# MCU.net
KiCad netlist of a schematic drawn in Altium Designer
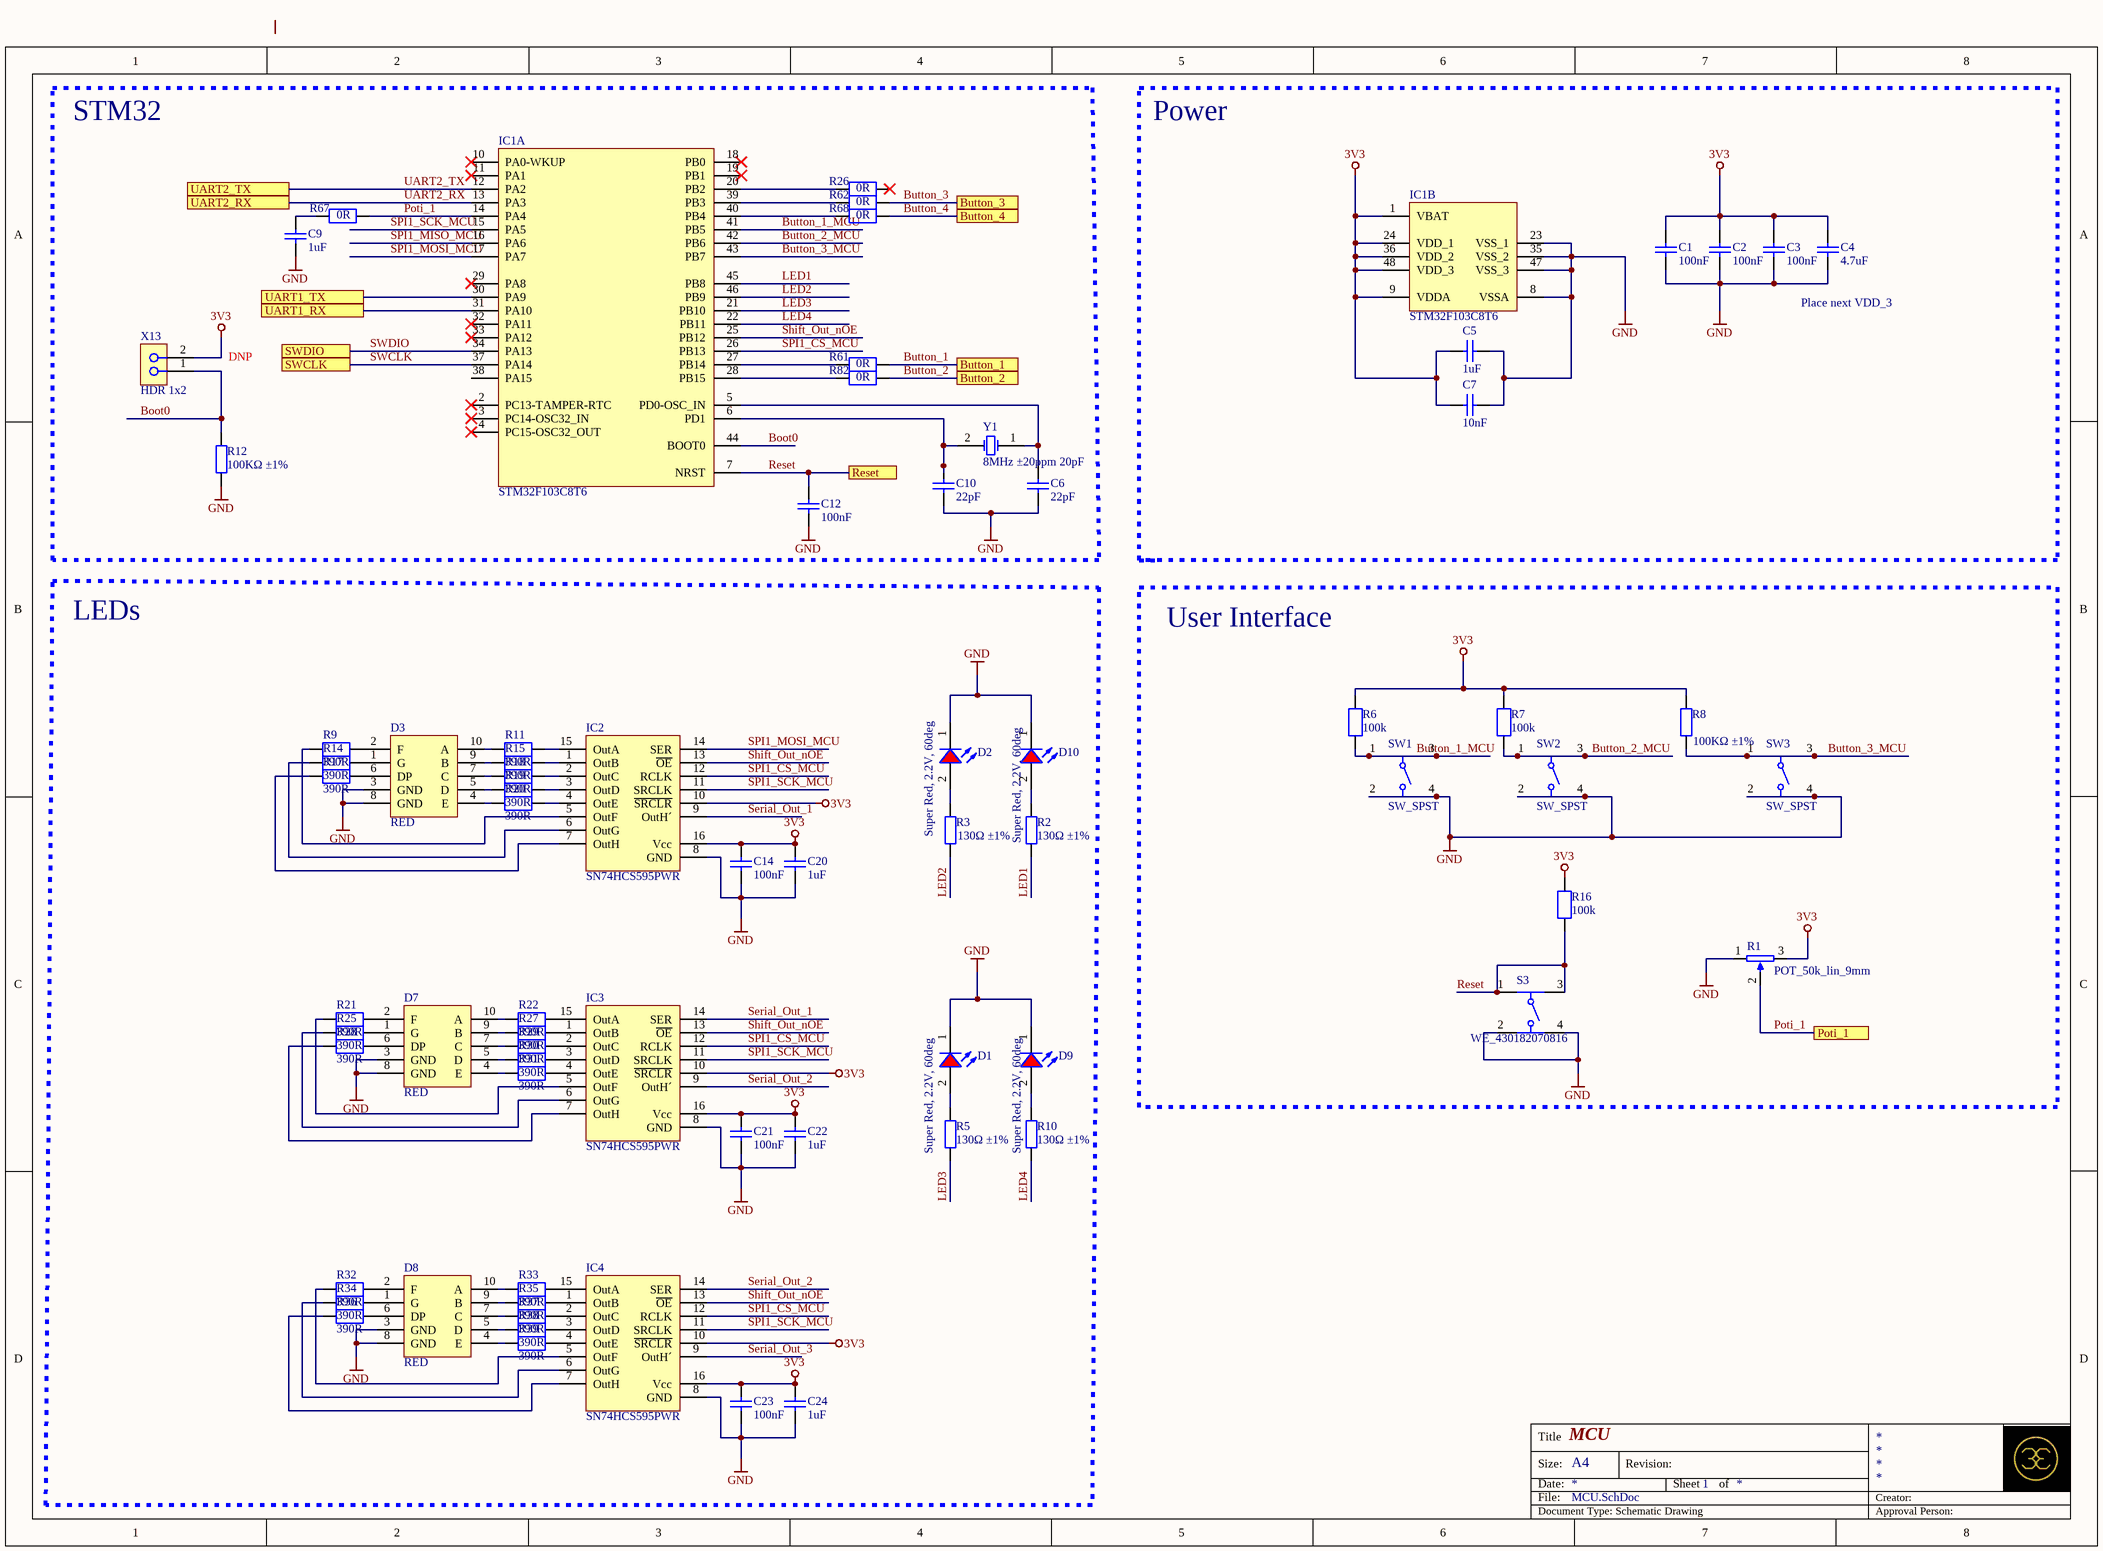
[diagram p0: MCU.SchDoc]

(export (version "E")
  (design (tool "Eeschema 10.0.6"))
  (components
    (comp (ref "C1")
      (value "100nF")
      (footprint "0603_C")
      (description "Chip capacitors")
      (fields (field (name "MANUFACTURER") "YAGEO") (field (name "PARTNUMBER") "CC0603KRX7R9BB104"))
      (libsource (lib "Cap") (part "0603 100nF (104) 10% 50V"))
    )
    (comp (ref "C2")
      (value "100nF")
      (footprint "0603_C")
      (description "Chip capacitors")
      (fields (field (name "MANUFACTURER") "YAGEO") (field (name "PARTNUMBER") "CC0603KRX7R9BB104"))
      (libsource (lib "Cap") (part "0603 100nF (104) 10% 50V"))
    )
    (comp (ref "C3")
      (value "100nF")
      (footprint "0603_C")
      (description "Chip capacitors")
      (fields (field (name "MANUFACTURER") "YAGEO") (field (name "PARTNUMBER") "CC0603KRX7R9BB104"))
      (libsource (lib "Cap") (part "0603 100nF (104) 10% 50V"))
    )
    (comp (ref "C4")
      (value "4.7uF")
      (footprint "0603_C")
      (description "Chip capacitors")
      (fields
        (field (name "MANUFACTURER") "Samsung Electro-Mechanics")
        (field (name "PARTNUMBER") "CL10A475KO8NNNC")
      )
      (libsource (lib "Cap") (part "0603 4.7uF (475) 10% 16V"))
    )
    (comp (ref "C5")
      (value "1uF")
      (footprint "0603_C")
      (description "Chip capacitors")
      (fields
        (field (name "MANUFACTURER") "Samsung Electro-Mechanics")
        (field (name "PARTNUMBER") "CL10A105KB8NNNC")
      )
      (libsource (lib "Cap") (part "0603 1uF (105) 10% 50V"))
    )
    (comp (ref "C6")
      (value "22pF")
      (footprint "0603_C")
      (description "Chip capacitors")
      (fields
        (field (name "MANUFACTURER") "Samsung Electro-Mechanics")
        (field (name "PARTNUMBER") "CL10C220JB8NNNC")
      )
      (libsource (lib "Cap") (part "0603 22pF (220) 5% 50V"))
    )
    (comp (ref "C7")
      (value "10nF")
      (footprint "0603_C")
      (description "Chip capacitors")
      (fields
        (field (name "MANUFACTURER") "Guangdong Fenghua Advanced Tech")
        (field (name "PARTNUMBER") "0603B103K500NT")
      )
      (libsource (lib "Cap") (part "0603 10nF (103) 10% 50V"))
    )
    (comp (ref "C9")
      (value "1uF")
      (footprint "0603_C")
      (description "Chip capacitors")
      (fields
        (field (name "MANUFACTURER") "Samsung Electro-Mechanics")
        (field (name "PARTNUMBER") "CL10A105KB8NNNC")
      )
      (libsource (lib "Cap") (part "0603 1uF (105) 10% 50V"))
    )
    (comp (ref "C10")
      (value "22pF")
      (footprint "0603_C")
      (description "Chip capacitors")
      (fields
        (field (name "MANUFACTURER") "Samsung Electro-Mechanics")
        (field (name "PARTNUMBER") "CL10C220JB8NNNC")
      )
      (libsource (lib "Cap") (part "0603 22pF (220) 5% 50V"))
    )
    (comp (ref "C12")
      (value "100nF")
      (footprint "0603_C")
      (description "Chip capacitors")
      (fields (field (name "MANUFACTURER") "YAGEO") (field (name "PARTNUMBER") "CC0603KRX7R9BB104"))
      (libsource (lib "Cap") (part "0603 100nF (104) 10% 50V"))
    )
    (comp (ref "C14")
      (value "100nF")
      (footprint "0603_C")
      (description "Chip capacitors")
      (fields (field (name "MANUFACTURER") "YAGEO") (field (name "PARTNUMBER") "CC0603KRX7R9BB104"))
      (libsource (lib "Cap") (part "0603 100nF (104) 10% 50V"))
    )
    (comp (ref "C20")
      (value "1uF")
      (footprint "0603_C")
      (description "Chip capacitors")
      (fields
        (field (name "MANUFACTURER") "Samsung Electro-Mechanics")
        (field (name "PARTNUMBER") "CL10A105KB8NNNC")
      )
      (libsource (lib "Cap") (part "0603 1uF (105) 10% 50V"))
    )
    (comp (ref "C21")
      (value "100nF")
      (footprint "0603_C")
      (description "Chip capacitors")
      (fields (field (name "MANUFACTURER") "YAGEO") (field (name "PARTNUMBER") "CC0603KRX7R9BB104"))
      (libsource (lib "Cap") (part "0603 100nF (104) 10% 50V"))
    )
    (comp (ref "C22")
      (value "1uF")
      (footprint "0603_C")
      (description "Chip capacitors")
      (fields
        (field (name "MANUFACTURER") "Samsung Electro-Mechanics")
        (field (name "PARTNUMBER") "CL10A105KB8NNNC")
      )
      (libsource (lib "Cap") (part "0603 1uF (105) 10% 50V"))
    )
    (comp (ref "C23")
      (value "100nF")
      (footprint "0603_C")
      (description "Chip capacitors")
      (fields (field (name "MANUFACTURER") "YAGEO") (field (name "PARTNUMBER") "CC0603KRX7R9BB104"))
      (libsource (lib "Cap") (part "0603 100nF (104) 10% 50V"))
    )
    (comp (ref "C24")
      (value "1uF")
      (footprint "0603_C")
      (description "Chip capacitors")
      (fields
        (field (name "MANUFACTURER") "Samsung Electro-Mechanics")
        (field (name "PARTNUMBER") "CL10A105KB8NNNC")
      )
      (libsource (lib "Cap") (part "0603 1uF (105) 10% 50V"))
    )
    (comp (ref "D1")
      (value "Super Red, 2.2V, 60deg")
      (footprint "WL-TMRC_3mm_10mm_space")
      (description "WL-TMRC THT Mono-color Round Color, size 3mm, Super Red, 2.2V, 60deg")
      (fields (field (name "PART NUMBER") "151031SS06000") (field (name "PUBLISHER") "Wurth Elektronik"))
      (libsource (lib "Diodes") (part "151031SS06000_Spacer_10mm"))
    )
    (comp (ref "D2")
      (value "Super Red, 2.2V, 60deg")
      (footprint "WL-TMRC_3mm_10mm_space")
      (description "WL-TMRC THT Mono-color Round Color, size 3mm, Super Red, 2.2V, 60deg")
      (fields (field (name "PART NUMBER") "151031SS06000") (field (name "PUBLISHER") "Wurth Elektronik"))
      (libsource (lib "Diodes") (part "151031SS06000_Spacer_10mm"))
    )
    (comp (ref "D3")
      (value "RED")
      (footprint "LTS-4301WC")
      (description "LED Displays & Accessories 1-Digit SMD Display Red Low-Cur .40")
      (fields (field (name "MANUFACTURER") "Lite-On") (field (name "MANUFACTURER PART NUMBER") "LTS-4301WC"))
      (libsource (lib "Diodes") (part "7-SEGMENT-10mm"))
    )
    (comp (ref "D7")
      (value "RED")
      (footprint "LTS-4301WC")
      (description "LED Displays & Accessories 1-Digit SMD Display Red Low-Cur .40")
      (fields (field (name "MANUFACTURER") "Lite-On") (field (name "MANUFACTURER PART NUMBER") "LTS-4301WC"))
      (libsource (lib "Diodes") (part "7-SEGMENT-10mm"))
    )
    (comp (ref "D8")
      (value "RED")
      (footprint "LTS-4301WC")
      (description "LED Displays & Accessories 1-Digit SMD Display Red Low-Cur .40")
      (fields (field (name "MANUFACTURER") "Lite-On") (field (name "MANUFACTURER PART NUMBER") "LTS-4301WC"))
      (libsource (lib "Diodes") (part "7-SEGMENT-10mm"))
    )
    (comp (ref "D9")
      (value "Super Red, 2.2V, 60deg")
      (footprint "WL-TMRC_3mm_10mm_space")
      (description "WL-TMRC THT Mono-color Round Color, size 3mm, Super Red, 2.2V, 60deg")
      (fields (field (name "PART NUMBER") "151031SS06000") (field (name "PUBLISHER") "Wurth Elektronik"))
      (libsource (lib "Diodes") (part "151031SS06000_Spacer_10mm"))
    )
    (comp (ref "D10")
      (value "Super Red, 2.2V, 60deg")
      (footprint "WL-TMRC_3mm_10mm_space")
      (description "WL-TMRC THT Mono-color Round Color, size 3mm, Super Red, 2.2V, 60deg")
      (fields (field (name "PART NUMBER") "151031SS06000") (field (name "PUBLISHER") "Wurth Elektronik"))
      (libsource (lib "Diodes") (part "151031SS06000_Spacer_10mm"))
    )
    (comp (ref "IC1")
      (value "STM32F103C8T6")
      (footprint "LQFP-48_7x7x05P")
      (description "ARM")
      (fields (field (name "MANUFACTURER") "STMicroelectronics"))
      (libsource (lib "ICs") (part "STM32F103C8T6"))
    )
    (comp (ref "IC2")
      (value "SN74HCS595PWR")
      (footprint "TSOP65P640X120-16N_2")
      (description "Counter Shift Registers 8-bit serial-in/parallel-out shift register 16-TSSOP -40 to 125")
      (fields (field (name "MANUFACTURER") "Texas Instruments"))
      (libsource (lib "ICs") (part "IC_SN74HCS595"))
    )
    (comp (ref "IC3")
      (value "SN74HCS595PWR")
      (footprint "TSOP65P640X120-16N_2")
      (description "Counter Shift Registers 8-bit serial-in/parallel-out shift register 16-TSSOP -40 to 125")
      (fields (field (name "MANUFACTURER") "Texas Instruments"))
      (libsource (lib "ICs") (part "IC_SN74HCS595"))
    )
    (comp (ref "IC4")
      (value "SN74HCS595PWR")
      (footprint "TSOP65P640X120-16N_2")
      (description "Counter Shift Registers 8-bit serial-in/parallel-out shift register 16-TSSOP -40 to 125")
      (fields (field (name "MANUFACTURER") "Texas Instruments"))
      (libsource (lib "ICs") (part "IC_SN74HCS595"))
    )
    (comp (ref "R1")
      (value "POT_50k_lin_9mm")
      (footprint "PTV09")
      (description "Potentiometers PANEL CONTROL - 9MM-ST-CA 50 kohms 30 mm")
      (fields
        (field (name "MANUFACTURER") "Bourns")
        (field (name "MANUFACTURER PART NUMBER") "PTV09A-4030S-A503")
      )
      (libsource (lib "Resistors") (part "POT_50k_lin_9mm"))
    )
    (comp (ref "R2")
      (value "130Ω ±1%")
      (footprint "0603_R")
      (description "Chip resistor")
      (fields (field (name "MANUFACTURER") "Uniroyal Elec") (field (name "PARTNUMBER") "0603WAF1300T5E"))
      (libsource (lib "RES") (part "0603 130R (1300) 1%"))
    )
    (comp (ref "R3")
      (value "130Ω ±1%")
      (footprint "0603_R")
      (description "Chip resistor")
      (fields (field (name "MANUFACTURER") "Uniroyal Elec") (field (name "PARTNUMBER") "0603WAF1300T5E"))
      (libsource (lib "RES") (part "0603 130R (1300) 1%"))
    )
    (comp (ref "R5")
      (value "130Ω ±1%")
      (footprint "0603_R")
      (description "Chip resistor")
      (fields (field (name "MANUFACTURER") "Uniroyal Elec") (field (name "PARTNUMBER") "0603WAF1300T5E"))
      (libsource (lib "RES") (part "0603 130R (1300) 1%"))
    )
    (comp (ref "R6")
      (value "100k")
      (footprint "RESC2012X70N")
      (description "Thick Film Resistors - SMD 1/8watt 100Kohms 1% 100ppm")
      (fields
        (field (name "MANUFACTURER") "Vishay / Dale")
        (field (name "MANUFACTURER PART NUMBER") "CRCW0805100KFKEA")
      )
      (libsource (lib "Resistors") (part "RES_100k_0805"))
    )
    (comp (ref "R7")
      (value "100k")
      (footprint "RESC2012X70N")
      (description "Thick Film Resistors - SMD 1/8watt 100Kohms 1% 100ppm")
      (fields
        (field (name "MANUFACTURER") "Vishay / Dale")
        (field (name "MANUFACTURER PART NUMBER") "CRCW0805100KFKEA")
      )
      (libsource (lib "Resistors") (part "RES_100k_0805"))
    )
    (comp (ref "R8")
      (value "100KΩ ±1%")
      (footprint "0603_R")
      (description "Chip resistor")
      (fields (field (name "MANUFACTURER") "Uniroyal Elec") (field (name "PARTNUMBER") "0603WAF1003T5E"))
      (libsource (lib "RES") (part "0603 100K (1003) 1%"))
    )
    (comp (ref "R9")
      (value "390R")
      (footprint "RESC2012X70N")
      (description "Thick Film Resistors - SMD 1/8Watt 390ohms 1% Commercial Use")
      (fields
        (field (name "MANUFACTURER") "Vishay / Dale")
        (field (name "MANUFACTURER PART NUMBER") "CRCW0805390RFKEA")
      )
      (libsource (lib "Resistors") (part "RES_390R_0805"))
    )
    (comp (ref "R10")
      (value "130Ω ±1%")
      (footprint "0603_R")
      (description "Chip resistor")
      (fields (field (name "MANUFACTURER") "Uniroyal Elec") (field (name "PARTNUMBER") "0603WAF1300T5E"))
      (libsource (lib "RES") (part "0603 130R (1300) 1%"))
    )
    (comp (ref "R11")
      (value "390R")
      (footprint "RESC2012X70N")
      (description "Thick Film Resistors - SMD 1/8Watt 390ohms 1% Commercial Use")
      (fields
        (field (name "MANUFACTURER") "Vishay / Dale")
        (field (name "MANUFACTURER PART NUMBER") "CRCW0805390RFKEA")
      )
      (libsource (lib "Resistors") (part "RES_390R_0805"))
    )
    (comp (ref "R12")
      (value "100KΩ ±1%")
      (footprint "0603_R")
      (description "Chip resistor")
      (fields (field (name "MANUFACTURER") "Uniroyal Elec") (field (name "PARTNUMBER") "0603WAF1003T5E"))
      (libsource (lib "RES") (part "0603 100K (1003) 1%"))
    )
    (comp (ref "R14")
      (value "390R")
      (footprint "RESC2012X70N")
      (description "Thick Film Resistors - SMD 1/8Watt 390ohms 1% Commercial Use")
      (fields
        (field (name "MANUFACTURER") "Vishay / Dale")
        (field (name "MANUFACTURER PART NUMBER") "CRCW0805390RFKEA")
      )
      (libsource (lib "Resistors") (part "RES_390R_0805"))
    )
    (comp (ref "R15")
      (value "390R")
      (footprint "RESC2012X70N")
      (description "Thick Film Resistors - SMD 1/8Watt 390ohms 1% Commercial Use")
      (fields
        (field (name "MANUFACTURER") "Vishay / Dale")
        (field (name "MANUFACTURER PART NUMBER") "CRCW0805390RFKEA")
      )
      (libsource (lib "Resistors") (part "RES_390R_0805"))
    )
    (comp (ref "R16")
      (value "100k")
      (footprint "RESC2012X70N")
      (description "Thick Film Resistors - SMD 1/8watt 100Kohms 1% 100ppm")
      (fields
        (field (name "MANUFACTURER") "Vishay / Dale")
        (field (name "MANUFACTURER PART NUMBER") "CRCW0805100KFKEA")
      )
      (libsource (lib "Resistors") (part "RES_100k_0805"))
    )
    (comp (ref "R17")
      (value "390R")
      (footprint "RESC2012X70N")
      (description "Thick Film Resistors - SMD 1/8Watt 390ohms 1% Commercial Use")
      (fields
        (field (name "MANUFACTURER") "Vishay / Dale")
        (field (name "MANUFACTURER PART NUMBER") "CRCW0805390RFKEA")
      )
      (libsource (lib "Resistors") (part "RES_390R_0805"))
    )
    (comp (ref "R18")
      (value "390R")
      (footprint "RESC2012X70N")
      (description "Thick Film Resistors - SMD 1/8Watt 390ohms 1% Commercial Use")
      (fields
        (field (name "MANUFACTURER") "Vishay / Dale")
        (field (name "MANUFACTURER PART NUMBER") "CRCW0805390RFKEA")
      )
      (libsource (lib "Resistors") (part "RES_390R_0805"))
    )
    (comp (ref "R19")
      (value "390R")
      (footprint "RESC2012X70N")
      (description "Thick Film Resistors - SMD 1/8Watt 390ohms 1% Commercial Use")
      (fields
        (field (name "MANUFACTURER") "Vishay / Dale")
        (field (name "MANUFACTURER PART NUMBER") "CRCW0805390RFKEA")
      )
      (libsource (lib "Resistors") (part "RES_390R_0805"))
    )
    (comp (ref "R20")
      (value "390R")
      (footprint "RESC2012X70N")
      (description "Thick Film Resistors - SMD 1/8Watt 390ohms 1% Commercial Use")
      (fields
        (field (name "MANUFACTURER") "Vishay / Dale")
        (field (name "MANUFACTURER PART NUMBER") "CRCW0805390RFKEA")
      )
      (libsource (lib "Resistors") (part "RES_390R_0805"))
    )
    (comp (ref "R21")
      (value "390R")
      (footprint "RESC2012X70N")
      (description "Thick Film Resistors - SMD 1/8Watt 390ohms 1% Commercial Use")
      (fields
        (field (name "MANUFACTURER") "Vishay / Dale")
        (field (name "MANUFACTURER PART NUMBER") "CRCW0805390RFKEA")
      )
      (libsource (lib "Resistors") (part "RES_390R_0805"))
    )
    (comp (ref "R22")
      (value "390R")
      (footprint "RESC2012X70N")
      (description "Thick Film Resistors - SMD 1/8Watt 390ohms 1% Commercial Use")
      (fields
        (field (name "MANUFACTURER") "Vishay / Dale")
        (field (name "MANUFACTURER PART NUMBER") "CRCW0805390RFKEA")
      )
      (libsource (lib "Resistors") (part "RES_390R_0805"))
    )
    (comp (ref "R25")
      (value "390R")
      (footprint "RESC2012X70N")
      (description "Thick Film Resistors - SMD 1/8Watt 390ohms 1% Commercial Use")
      (fields
        (field (name "MANUFACTURER") "Vishay / Dale")
        (field (name "MANUFACTURER PART NUMBER") "CRCW0805390RFKEA")
      )
      (libsource (lib "Resistors") (part "RES_390R_0805"))
    )
    (comp (ref "R26")
      (value "0R")
      (footprint "RESC1608X55N")
      (description "Thick Film Resistors - SMD 1/10watt ZEROohm Jumper")
      (fields
        (field (name "MANUFACTURER") "Vishay")
        (field (name "MANUFACTURER PART NUMBER") "CRCW06030000Z0EA")
      )
      (libsource (lib "Resistors") (part "RES_0R_0603"))
    )
    (comp (ref "R27")
      (value "390R")
      (footprint "RESC2012X70N")
      (description "Thick Film Resistors - SMD 1/8Watt 390ohms 1% Commercial Use")
      (fields
        (field (name "MANUFACTURER") "Vishay / Dale")
        (field (name "MANUFACTURER PART NUMBER") "CRCW0805390RFKEA")
      )
      (libsource (lib "Resistors") (part "RES_390R_0805"))
    )
    (comp (ref "R28")
      (value "390R")
      (footprint "RESC2012X70N")
      (description "Thick Film Resistors - SMD 1/8Watt 390ohms 1% Commercial Use")
      (fields
        (field (name "MANUFACTURER") "Vishay / Dale")
        (field (name "MANUFACTURER PART NUMBER") "CRCW0805390RFKEA")
      )
      (libsource (lib "Resistors") (part "RES_390R_0805"))
    )
    (comp (ref "R29")
      (value "390R")
      (footprint "RESC2012X70N")
      (description "Thick Film Resistors - SMD 1/8Watt 390ohms 1% Commercial Use")
      (fields
        (field (name "MANUFACTURER") "Vishay / Dale")
        (field (name "MANUFACTURER PART NUMBER") "CRCW0805390RFKEA")
      )
      (libsource (lib "Resistors") (part "RES_390R_0805"))
    )
    (comp (ref "R30")
      (value "390R")
      (footprint "RESC2012X70N")
      (description "Thick Film Resistors - SMD 1/8Watt 390ohms 1% Commercial Use")
      (fields
        (field (name "MANUFACTURER") "Vishay / Dale")
        (field (name "MANUFACTURER PART NUMBER") "CRCW0805390RFKEA")
      )
      (libsource (lib "Resistors") (part "RES_390R_0805"))
    )
    (comp (ref "R31")
      (value "390R")
      (footprint "RESC2012X70N")
      (description "Thick Film Resistors - SMD 1/8Watt 390ohms 1% Commercial Use")
      (fields
        (field (name "MANUFACTURER") "Vishay / Dale")
        (field (name "MANUFACTURER PART NUMBER") "CRCW0805390RFKEA")
      )
      (libsource (lib "Resistors") (part "RES_390R_0805"))
    )
    (comp (ref "R32")
      (value "390R")
      (footprint "RESC2012X70N")
      (description "Thick Film Resistors - SMD 1/8Watt 390ohms 1% Commercial Use")
      (fields
        (field (name "MANUFACTURER") "Vishay / Dale")
        (field (name "MANUFACTURER PART NUMBER") "CRCW0805390RFKEA")
      )
      (libsource (lib "Resistors") (part "RES_390R_0805"))
    )
    (comp (ref "R33")
      (value "390R")
      (footprint "RESC2012X70N")
      (description "Thick Film Resistors - SMD 1/8Watt 390ohms 1% Commercial Use")
      (fields
        (field (name "MANUFACTURER") "Vishay / Dale")
        (field (name "MANUFACTURER PART NUMBER") "CRCW0805390RFKEA")
      )
      (libsource (lib "Resistors") (part "RES_390R_0805"))
    )
    (comp (ref "R34")
      (value "390R")
      (footprint "RESC2012X70N")
      (description "Thick Film Resistors - SMD 1/8Watt 390ohms 1% Commercial Use")
      (fields
        (field (name "MANUFACTURER") "Vishay / Dale")
        (field (name "MANUFACTURER PART NUMBER") "CRCW0805390RFKEA")
      )
      (libsource (lib "Resistors") (part "RES_390R_0805"))
    )
    (comp (ref "R35")
      (value "390R")
      (footprint "RESC2012X70N")
      (description "Thick Film Resistors - SMD 1/8Watt 390ohms 1% Commercial Use")
      (fields
        (field (name "MANUFACTURER") "Vishay / Dale")
        (field (name "MANUFACTURER PART NUMBER") "CRCW0805390RFKEA")
      )
      (libsource (lib "Resistors") (part "RES_390R_0805"))
    )
    (comp (ref "R36")
      (value "390R")
      (footprint "RESC2012X70N")
      (description "Thick Film Resistors - SMD 1/8Watt 390ohms 1% Commercial Use")
      (fields
        (field (name "MANUFACTURER") "Vishay / Dale")
        (field (name "MANUFACTURER PART NUMBER") "CRCW0805390RFKEA")
      )
      (libsource (lib "Resistors") (part "RES_390R_0805"))
    )
    (comp (ref "R37")
      (value "390R")
      (footprint "RESC2012X70N")
      (description "Thick Film Resistors - SMD 1/8Watt 390ohms 1% Commercial Use")
      (fields
        (field (name "MANUFACTURER") "Vishay / Dale")
        (field (name "MANUFACTURER PART NUMBER") "CRCW0805390RFKEA")
      )
      (libsource (lib "Resistors") (part "RES_390R_0805"))
    )
    (comp (ref "R38")
      (value "390R")
      (footprint "RESC2012X70N")
      (description "Thick Film Resistors - SMD 1/8Watt 390ohms 1% Commercial Use")
      (fields
        (field (name "MANUFACTURER") "Vishay / Dale")
        (field (name "MANUFACTURER PART NUMBER") "CRCW0805390RFKEA")
      )
      (libsource (lib "Resistors") (part "RES_390R_0805"))
    )
    (comp (ref "R39")
      (value "390R")
      (footprint "RESC2012X70N")
      (description "Thick Film Resistors - SMD 1/8Watt 390ohms 1% Commercial Use")
      (fields
        (field (name "MANUFACTURER") "Vishay / Dale")
        (field (name "MANUFACTURER PART NUMBER") "CRCW0805390RFKEA")
      )
      (libsource (lib "Resistors") (part "RES_390R_0805"))
    )
    (comp (ref "R61")
      (value "0R")
      (footprint "RESC1608X55N")
      (description "Thick Film Resistors - SMD 1/10watt ZEROohm Jumper")
      (fields
        (field (name "MANUFACTURER") "Vishay")
        (field (name "MANUFACTURER PART NUMBER") "CRCW06030000Z0EA")
      )
      (libsource (lib "Resistors") (part "RES_0R_0603"))
    )
    (comp (ref "R62")
      (value "0R")
      (footprint "RESC1608X55N")
      (description "Thick Film Resistors - SMD 1/10watt ZEROohm Jumper")
      (fields
        (field (name "MANUFACTURER") "Vishay")
        (field (name "MANUFACTURER PART NUMBER") "CRCW06030000Z0EA")
      )
      (libsource (lib "Resistors") (part "RES_0R_0603"))
    )
    (comp (ref "R67")
      (value "0R")
      (footprint "RESC1608X55N")
      (description "Thick Film Resistors - SMD 1/10watt ZEROohm Jumper")
      (fields
        (field (name "MANUFACTURER") "Vishay")
        (field (name "MANUFACTURER PART NUMBER") "CRCW06030000Z0EA")
      )
      (libsource (lib "Resistors") (part "RES_0R_0603"))
    )
    (comp (ref "R68")
      (value "0R")
      (footprint "RESC1608X55N")
      (description "Thick Film Resistors - SMD 1/10watt ZEROohm Jumper")
      (fields
        (field (name "MANUFACTURER") "Vishay")
        (field (name "MANUFACTURER PART NUMBER") "CRCW06030000Z0EA")
      )
      (libsource (lib "Resistors") (part "RES_0R_0603"))
    )
    (comp (ref "R82")
      (value "0R")
      (footprint "RESC1608X55N")
      (description "Thick Film Resistors - SMD 1/10watt ZEROohm Jumper")
      (fields
        (field (name "MANUFACTURER") "Vishay")
        (field (name "MANUFACTURER PART NUMBER") "CRCW06030000Z0EA")
      )
      (libsource (lib "Resistors") (part "RES_0R_0603"))
    )
    (comp (ref "S3")
      (value "WE_430182070816")
      (footprint "430182070816")
      (description "WS-TASV SMT Tact Switch 6x6mm, height 7mm, 160gf")
      (fields (field (name "PART NUMBER") "430182070816") (field (name "PUBLISHER") "Wurth Elektronik"))
      (libsource (lib "Switches") (part "WE_430182070816"))
    )
    (comp (ref "SW1")
      (value "SW_SPST")
      (footprint "TL1105D")
      (description "Tastschalter SPST-Schließer Von oben betätigt Durchkontaktierung")
      (fields
        (field (name "MANUFACTURER") "E-Switch")
        (field (name "MANUFACTURER PART NUMBER") "TL1105DF160Q")
      )
      (libsource (lib "Switches") (part "SW_ TL1105DF160Q"))
    )
    (comp (ref "SW2")
      (value "SW_SPST")
      (footprint "TL1105D")
      (description "Tastschalter SPST-Schließer Von oben betätigt Durchkontaktierung")
      (fields
        (field (name "MANUFACTURER") "E-Switch")
        (field (name "MANUFACTURER PART NUMBER") "TL1105DF160Q")
      )
      (libsource (lib "Switches") (part "SW_ TL1105DF160Q"))
    )
    (comp (ref "SW3")
      (value "SW_SPST")
      (footprint "TL1105D")
      (description "Tastschalter SPST-Schließer Von oben betätigt Durchkontaktierung")
      (fields
        (field (name "MANUFACTURER") "E-Switch")
        (field (name "MANUFACTURER PART NUMBER") "TL1105DF160Q")
      )
      (libsource (lib "Switches") (part "SW_ TL1105DF160Q"))
    )
    (comp (ref "X13")
      (value "HDR 1x2")
      (footprint "CON_HEADER2.54_1x2W")
      (description "Board-to-Board-Steckverbinder, 2.54 mm, 2 Kontakt(e), Stiftleiste 1-Reihig")
      (fields
        (field (name "MANUFACTURER") "Samtec")
        (field (name "MANUFACTURER PART NUMBER") "TSW-102-07-T-S")
      )
      (libsource (lib "Connectors") (part "CON_HEADER_1X2"))
    )
    (comp (ref "Y1")
      (value "8MHz ±20ppm 20pF")
      (footprint "SMD-5032_2P")
      (description "贴片晶振")
      (libsource (lib "CrystalOscillator") (part "SMD-5032_2P 8MHz 20ppm 20pF"))
    )
  )
  (nets
    (net (code "1") (name "/Boot0") (class "Default")
      (node (ref "IC1") (pin "44") (pinfunction "BOOT0_44") (pintype "passive"))
      (node (ref "R12") (pin "2") (pinfunction "2_2") (pintype "passive"))
      (node (ref "X13") (pin "1") (pinfunction "1_1") (pintype "passive"))
    )
    (net (code "2") (name "/Button_1") (class "Default")
      (node (ref "R61") (pin "2") (pinfunction "2_2") (pintype "passive"))
    )
    (net (code "3") (name "/Button_1_MCU") (class "Default")
      (node (ref "IC1") (pin "41") (pinfunction "PB5_41") (pintype "passive"))
      (node (ref "R6") (pin "1") (pinfunction "1_1") (pintype "passive"))
      (node (ref "SW1") (pin "1") (pinfunction "1_1") (pintype "passive"))
      (node (ref "SW1") (pin "3") (pinfunction "3_3") (pintype "passive"))
    )
    (net (code "4") (name "/Button_2") (class "Default")
      (node (ref "R82") (pin "2") (pinfunction "2_2") (pintype "passive"))
    )
    (net (code "5") (name "/Button_2_MCU") (class "Default")
      (node (ref "IC1") (pin "42") (pinfunction "PB6_42") (pintype "passive"))
      (node (ref "R7") (pin "1") (pinfunction "1_1") (pintype "passive"))
      (node (ref "SW2") (pin "1") (pinfunction "1_1") (pintype "passive"))
      (node (ref "SW2") (pin "3") (pinfunction "3_3") (pintype "passive"))
    )
    (net (code "6") (name "/Button_3") (class "Default")
      (node (ref "R62") (pin "2") (pinfunction "2_2") (pintype "passive"))
    )
    (net (code "7") (name "/Button_3_MCU") (class "Default")
      (node (ref "IC1") (pin "43") (pinfunction "PB7_43") (pintype "passive"))
      (node (ref "R8") (pin "1") (pinfunction "1_1") (pintype "passive"))
      (node (ref "SW3") (pin "1") (pinfunction "1_1") (pintype "passive"))
      (node (ref "SW3") (pin "3") (pinfunction "3_3") (pintype "passive"))
    )
    (net (code "8") (name "/Button_4") (class "Default")
      (node (ref "R68") (pin "2") (pinfunction "2_2") (pintype "passive"))
    )
    (net (code "9") (name "/LED1") (class "Default")
      (node (ref "IC1") (pin "45") (pinfunction "PB8_45") (pintype "passive"))
      (node (ref "R2") (pin "2") (pinfunction "2_2") (pintype "passive"))
    )
    (net (code "10") (name "/LED2") (class "Default")
      (node (ref "IC1") (pin "46") (pinfunction "PB9_46") (pintype "passive"))
      (node (ref "R3") (pin "2") (pinfunction "2_2") (pintype "passive"))
    )
    (net (code "11") (name "/LED3") (class "Default")
      (node (ref "IC1") (pin "21") (pinfunction "PB10_21") (pintype "passive"))
      (node (ref "R5") (pin "2") (pinfunction "2_2") (pintype "passive"))
    )
    (net (code "12") (name "/LED4") (class "Default")
      (node (ref "IC1") (pin "22") (pinfunction "PB11_22") (pintype "passive"))
      (node (ref "R10") (pin "2") (pinfunction "2_2") (pintype "passive"))
    )
    (net (code "13") (name "/Poti_1") (class "Default")
      (node (ref "IC1") (pin "14") (pinfunction "PA4_14") (pintype "passive"))
      (node (ref "R1") (pin "2") (pinfunction "2_2") (pintype "passive"))
      (node (ref "R67") (pin "2") (pinfunction "2_2") (pintype "passive"))
    )
    (net (code "14") (name "/Reset") (class "Default")
      (node (ref "C12") (pin "2") (pinfunction "2_2") (pintype "passive"))
      (node (ref "IC1") (pin "7") (pinfunction "NRST_7") (pintype "passive"))
      (node (ref "R16") (pin "1") (pinfunction "1_1") (pintype "passive"))
      (node (ref "S3") (pin "1") (pinfunction "1_1") (pintype "passive"))
      (node (ref "S3") (pin "3") (pinfunction "3_3") (pintype "passive"))
    )
    (net (code "15") (name "/SPI1_CS_MCU") (class "Default")
      (node (ref "IC1") (pin "26") (pinfunction "PB13_26") (pintype "passive"))
      (node (ref "IC2") (pin "12") (pinfunction "RCLK_12") (pintype "passive"))
      (node (ref "IC3") (pin "12") (pinfunction "RCLK_12") (pintype "passive"))
      (node (ref "IC4") (pin "12") (pinfunction "RCLK_12") (pintype "passive"))
    )
    (net (code "16") (name "/SPI1_MISO_MCU") (class "Default")
      (node (ref "IC1") (pin "16") (pinfunction "PA6_16") (pintype "passive"))
    )
    (net (code "17") (name "/SPI1_MOSI_MCU") (class "Default")
      (node (ref "IC1") (pin "17") (pinfunction "PA7_17") (pintype "passive"))
      (node (ref "IC2") (pin "14") (pinfunction "SER_14") (pintype "passive"))
    )
    (net (code "18") (name "/SPI1_SCK_MCU") (class "Default")
      (node (ref "IC1") (pin "15") (pinfunction "PA5_15") (pintype "passive"))
      (node (ref "IC2") (pin "11") (pinfunction "SRCLK_11") (pintype "passive"))
      (node (ref "IC3") (pin "11") (pinfunction "SRCLK_11") (pintype "passive"))
      (node (ref "IC4") (pin "11") (pinfunction "SRCLK_11") (pintype "passive"))
    )
    (net (code "19") (name "/SWCLK") (class "Default")
      (node (ref "IC1") (pin "37") (pinfunction "PA14_37") (pintype "passive"))
    )
    (net (code "20") (name "/SWDIO") (class "Default")
      (node (ref "IC1") (pin "34") (pinfunction "PA13_34") (pintype "passive"))
    )
    (net (code "21") (name "/Serial_Out_1") (class "Default")
      (node (ref "IC2") (pin "9") (pinfunction "OutH´_9") (pintype "passive"))
      (node (ref "IC3") (pin "14") (pinfunction "SER_14") (pintype "passive"))
    )
    (net (code "22") (name "/Serial_Out_2") (class "Default")
      (node (ref "IC3") (pin "9") (pinfunction "OutH´_9") (pintype "passive"))
      (node (ref "IC4") (pin "14") (pinfunction "SER_14") (pintype "passive"))
    )
    (net (code "23") (name "/Serial_Out_3") (class "Default")
      (node (ref "IC4") (pin "9") (pinfunction "OutH´_9") (pintype "passive"))
    )
    (net (code "24") (name "/Shift_Out_nOE") (class "Default")
      (node (ref "IC1") (pin "25") (pinfunction "PB12_25") (pintype "passive"))
      (node (ref "IC2") (pin "13") (pinfunction "~{OE}_13") (pintype "passive"))
      (node (ref "IC3") (pin "13") (pinfunction "~{OE}_13") (pintype "passive"))
      (node (ref "IC4") (pin "13") (pinfunction "~{OE}_13") (pintype "passive"))
    )
    (net (code "25") (name "/UART1_RX") (class "Default")
      (node (ref "IC1") (pin "31") (pinfunction "PA10_31") (pintype "passive"))
    )
    (net (code "26") (name "/UART1_TX") (class "Default")
      (node (ref "IC1") (pin "30") (pinfunction "PA9_30") (pintype "passive"))
    )
    (net (code "27") (name "/UART2_RX") (class "Default")
      (node (ref "IC1") (pin "13") (pinfunction "PA3_13") (pintype "passive"))
    )
    (net (code "28") (name "/UART2_TX") (class "Default")
      (node (ref "IC1") (pin "12") (pinfunction "PA2_12") (pintype "passive"))
    )
    (net (code "29") (name "3V3") (class "Default")
      (node (ref "C1") (pin "2") (pinfunction "2_2") (pintype "passive"))
      (node (ref "C14") (pin "2") (pinfunction "2_2") (pintype "passive"))
      (node (ref "C2") (pin "2") (pinfunction "2_2") (pintype "passive"))
      (node (ref "C20") (pin "2") (pinfunction "2_2") (pintype "passive"))
      (node (ref "C21") (pin "2") (pinfunction "2_2") (pintype "passive"))
      (node (ref "C22") (pin "2") (pinfunction "2_2") (pintype "passive"))
      (node (ref "C23") (pin "2") (pinfunction "2_2") (pintype "passive"))
      (node (ref "C24") (pin "2") (pinfunction "2_2") (pintype "passive"))
      (node (ref "C3") (pin "2") (pinfunction "2_2") (pintype "passive"))
      (node (ref "C4") (pin "2") (pinfunction "2_2") (pintype "passive"))
      (node (ref "C5") (pin "1") (pinfunction "1_1") (pintype "passive"))
      (node (ref "C7") (pin "1") (pinfunction "1_1") (pintype "passive"))
      (node (ref "IC1") (pin "1") (pinfunction "VBAT_1") (pintype "power_in"))
      (node (ref "IC1") (pin "24") (pinfunction "VDD_1_24") (pintype "power_in"))
      (node (ref "IC1") (pin "36") (pinfunction "VDD_2_36") (pintype "power_in"))
      (node (ref "IC1") (pin "48") (pinfunction "VDD_3_48") (pintype "power_in"))
      (node (ref "IC1") (pin "9") (pinfunction "VDDA_9") (pintype "power_in"))
      (node (ref "IC2") (pin "10") (pinfunction "~{SRCLR}_10") (pintype "passive"))
      (node (ref "IC2") (pin "16") (pinfunction "Vcc_16") (pintype "passive"))
      (node (ref "IC3") (pin "10") (pinfunction "~{SRCLR}_10") (pintype "passive"))
      (node (ref "IC3") (pin "16") (pinfunction "Vcc_16") (pintype "passive"))
      (node (ref "IC4") (pin "10") (pinfunction "~{SRCLR}_10") (pintype "passive"))
      (node (ref "IC4") (pin "16") (pinfunction "Vcc_16") (pintype "passive"))
      (node (ref "R1") (pin "3") (pinfunction "3_3") (pintype "passive"))
      (node (ref "R16") (pin "2") (pinfunction "2_2") (pintype "passive"))
      (node (ref "R6") (pin "2") (pinfunction "2_2") (pintype "passive"))
      (node (ref "R7") (pin "2") (pinfunction "2_2") (pintype "passive"))
      (node (ref "R8") (pin "2") (pinfunction "2_2") (pintype "passive"))
      (node (ref "X13") (pin "2") (pinfunction "2_2") (pintype "passive"))
    )
    (net (code "30") (name "GND") (class "Default")
      (node (ref "C1") (pin "1") (pinfunction "1_1") (pintype "passive"))
      (node (ref "C10") (pin "2") (pinfunction "2_2") (pintype "passive"))
      (node (ref "C12") (pin "1") (pinfunction "1_1") (pintype "passive"))
      (node (ref "C14") (pin "1") (pinfunction "1_1") (pintype "passive"))
      (node (ref "C2") (pin "1") (pinfunction "1_1") (pintype "passive"))
      (node (ref "C20") (pin "1") (pinfunction "1_1") (pintype "passive"))
      (node (ref "C21") (pin "1") (pinfunction "1_1") (pintype "passive"))
      (node (ref "C22") (pin "1") (pinfunction "1_1") (pintype "passive"))
      (node (ref "C23") (pin "1") (pinfunction "1_1") (pintype "passive"))
      (node (ref "C24") (pin "1") (pinfunction "1_1") (pintype "passive"))
      (node (ref "C3") (pin "1") (pinfunction "1_1") (pintype "passive"))
      (node (ref "C4") (pin "1") (pinfunction "1_1") (pintype "passive"))
      (node (ref "C5") (pin "2") (pinfunction "2_2") (pintype "passive"))
      (node (ref "C6") (pin "2") (pinfunction "2_2") (pintype "passive"))
      (node (ref "C7") (pin "2") (pinfunction "2_2") (pintype "passive"))
      (node (ref "C9") (pin "2") (pinfunction "2_2") (pintype "passive"))
      (node (ref "D1") (pin "1") (pinfunction "K_1") (pintype "passive"))
      (node (ref "D10") (pin "1") (pinfunction "K_1") (pintype "passive"))
      (node (ref "D2") (pin "1") (pinfunction "K_1") (pintype "passive"))
      (node (ref "D3") (pin "3") (pinfunction "GND_3") (pintype "passive"))
      (node (ref "D3") (pin "8") (pinfunction "GND_8") (pintype "passive"))
      (node (ref "D7") (pin "3") (pinfunction "GND_3") (pintype "passive"))
      (node (ref "D7") (pin "8") (pinfunction "GND_8") (pintype "passive"))
      (node (ref "D8") (pin "3") (pinfunction "GND_3") (pintype "passive"))
      (node (ref "D8") (pin "8") (pinfunction "GND_8") (pintype "passive"))
      (node (ref "D9") (pin "1") (pinfunction "K_1") (pintype "passive"))
      (node (ref "IC1") (pin "23") (pinfunction "VSS_1_23") (pintype "power_in"))
      (node (ref "IC1") (pin "35") (pinfunction "VSS_2_35") (pintype "power_in"))
      (node (ref "IC1") (pin "47") (pinfunction "VSS_3_47") (pintype "power_in"))
      (node (ref "IC1") (pin "8") (pinfunction "VSSA_8") (pintype "power_in"))
      (node (ref "IC2") (pin "8") (pinfunction "GND_8") (pintype "passive"))
      (node (ref "IC3") (pin "8") (pinfunction "GND_8") (pintype "passive"))
      (node (ref "IC4") (pin "8") (pinfunction "GND_8") (pintype "passive"))
      (node (ref "R1") (pin "1") (pinfunction "1_1") (pintype "passive"))
      (node (ref "R12") (pin "1") (pinfunction "1_1") (pintype "passive"))
      (node (ref "S3") (pin "2") (pinfunction "2_2") (pintype "passive"))
      (node (ref "S3") (pin "4") (pinfunction "4_4") (pintype "passive"))
      (node (ref "SW1") (pin "2") (pinfunction "2_2") (pintype "passive"))
      (node (ref "SW1") (pin "4") (pinfunction "4_4") (pintype "passive"))
      (node (ref "SW2") (pin "2") (pinfunction "2_2") (pintype "passive"))
      (node (ref "SW2") (pin "4") (pinfunction "4_4") (pintype "passive"))
      (node (ref "SW3") (pin "2") (pinfunction "2_2") (pintype "passive"))
      (node (ref "SW3") (pin "4") (pinfunction "4_4") (pintype "passive"))
    )
    (net (code "31") (name "Net-(C9-Pad1)") (class "Default")
      (node (ref "C9") (pin "1") (pinfunction "1_1") (pintype "passive"))
      (node (ref "R67") (pin "1") (pinfunction "1_1") (pintype "passive"))
    )
    (net (code "32") (name "Net-(D1-A)") (class "Default")
      (node (ref "D1") (pin "2") (pinfunction "A_2") (pintype "passive"))
      (node (ref "R5") (pin "1") (pinfunction "1_1") (pintype "passive"))
    )
    (net (code "33") (name "Net-(D2-A)") (class "Default")
      (node (ref "D2") (pin "2") (pinfunction "A_2") (pintype "passive"))
      (node (ref "R3") (pin "1") (pinfunction "1_1") (pintype "passive"))
    )
    (net (code "34") (name "Net-(D3-A)") (class "Default")
      (node (ref "D3") (pin "10") (pinfunction "A_10") (pintype "passive"))
      (node (ref "R11") (pin "1") (pinfunction "1_1") (pintype "passive"))
    )
    (net (code "35") (name "Net-(D3-B)") (class "Default")
      (node (ref "D3") (pin "9") (pinfunction "B_9") (pintype "passive"))
      (node (ref "R15") (pin "1") (pinfunction "1_1") (pintype "passive"))
    )
    (net (code "36") (name "Net-(D3-C)") (class "Default")
      (node (ref "D3") (pin "7") (pinfunction "C_7") (pintype "passive"))
      (node (ref "R18") (pin "1") (pinfunction "1_1") (pintype "passive"))
    )
    (net (code "37") (name "Net-(D3-D)") (class "Default")
      (node (ref "D3") (pin "5") (pinfunction "D_5") (pintype "passive"))
      (node (ref "R19") (pin "1") (pinfunction "1_1") (pintype "passive"))
    )
    (net (code "38") (name "Net-(D3-DP)") (class "Default")
      (node (ref "D3") (pin "6") (pinfunction "DP_6") (pintype "passive"))
      (node (ref "R17") (pin "2") (pinfunction "2_2") (pintype "passive"))
    )
    (net (code "39") (name "Net-(D3-E)") (class "Default")
      (node (ref "D3") (pin "4") (pinfunction "E_4") (pintype "passive"))
      (node (ref "R20") (pin "1") (pinfunction "1_1") (pintype "passive"))
    )
    (net (code "40") (name "Net-(D3-F)") (class "Default")
      (node (ref "D3") (pin "2") (pinfunction "F_2") (pintype "passive"))
      (node (ref "R9") (pin "2") (pinfunction "2_2") (pintype "passive"))
    )
    (net (code "41") (name "Net-(D3-G)") (class "Default")
      (node (ref "D3") (pin "1") (pinfunction "G_1") (pintype "passive"))
      (node (ref "R14") (pin "2") (pinfunction "2_2") (pintype "passive"))
    )
    (net (code "42") (name "Net-(D7-A)") (class "Default")
      (node (ref "D7") (pin "10") (pinfunction "A_10") (pintype "passive"))
      (node (ref "R22") (pin "1") (pinfunction "1_1") (pintype "passive"))
    )
    (net (code "43") (name "Net-(D7-B)") (class "Default")
      (node (ref "D7") (pin "9") (pinfunction "B_9") (pintype "passive"))
      (node (ref "R27") (pin "1") (pinfunction "1_1") (pintype "passive"))
    )
    (net (code "44") (name "Net-(D7-C)") (class "Default")
      (node (ref "D7") (pin "7") (pinfunction "C_7") (pintype "passive"))
      (node (ref "R29") (pin "1") (pinfunction "1_1") (pintype "passive"))
    )
    (net (code "45") (name "Net-(D7-D)") (class "Default")
      (node (ref "D7") (pin "5") (pinfunction "D_5") (pintype "passive"))
      (node (ref "R30") (pin "1") (pinfunction "1_1") (pintype "passive"))
    )
    (net (code "46") (name "Net-(D7-DP)") (class "Default")
      (node (ref "D7") (pin "6") (pinfunction "DP_6") (pintype "passive"))
      (node (ref "R28") (pin "2") (pinfunction "2_2") (pintype "passive"))
    )
    (net (code "47") (name "Net-(D7-E)") (class "Default")
      (node (ref "D7") (pin "4") (pinfunction "E_4") (pintype "passive"))
      (node (ref "R31") (pin "1") (pinfunction "1_1") (pintype "passive"))
    )
    (net (code "48") (name "Net-(D7-F)") (class "Default")
      (node (ref "D7") (pin "2") (pinfunction "F_2") (pintype "passive"))
      (node (ref "R21") (pin "2") (pinfunction "2_2") (pintype "passive"))
    )
    (net (code "49") (name "Net-(D7-G)") (class "Default")
      (node (ref "D7") (pin "1") (pinfunction "G_1") (pintype "passive"))
      (node (ref "R25") (pin "2") (pinfunction "2_2") (pintype "passive"))
    )
    (net (code "50") (name "Net-(D8-A)") (class "Default")
      (node (ref "D8") (pin "10") (pinfunction "A_10") (pintype "passive"))
      (node (ref "R33") (pin "1") (pinfunction "1_1") (pintype "passive"))
    )
    (net (code "51") (name "Net-(D8-B)") (class "Default")
      (node (ref "D8") (pin "9") (pinfunction "B_9") (pintype "passive"))
      (node (ref "R35") (pin "1") (pinfunction "1_1") (pintype "passive"))
    )
    (net (code "52") (name "Net-(D8-C)") (class "Default")
      (node (ref "D8") (pin "7") (pinfunction "C_7") (pintype "passive"))
      (node (ref "R37") (pin "1") (pinfunction "1_1") (pintype "passive"))
    )
    (net (code "53") (name "Net-(D8-D)") (class "Default")
      (node (ref "D8") (pin "5") (pinfunction "D_5") (pintype "passive"))
      (node (ref "R38") (pin "1") (pinfunction "1_1") (pintype "passive"))
    )
    (net (code "54") (name "Net-(D8-DP)") (class "Default")
      (node (ref "D8") (pin "6") (pinfunction "DP_6") (pintype "passive"))
      (node (ref "R36") (pin "2") (pinfunction "2_2") (pintype "passive"))
    )
    (net (code "55") (name "Net-(D8-E)") (class "Default")
      (node (ref "D8") (pin "4") (pinfunction "E_4") (pintype "passive"))
      (node (ref "R39") (pin "1") (pinfunction "1_1") (pintype "passive"))
    )
    (net (code "56") (name "Net-(D8-F)") (class "Default")
      (node (ref "D8") (pin "2") (pinfunction "F_2") (pintype "passive"))
      (node (ref "R32") (pin "2") (pinfunction "2_2") (pintype "passive"))
    )
    (net (code "57") (name "Net-(D8-G)") (class "Default")
      (node (ref "D8") (pin "1") (pinfunction "G_1") (pintype "passive"))
      (node (ref "R34") (pin "2") (pinfunction "2_2") (pintype "passive"))
    )
    (net (code "58") (name "Net-(D9-A)") (class "Default")
      (node (ref "D9") (pin "2") (pinfunction "A_2") (pintype "passive"))
      (node (ref "R10") (pin "1") (pinfunction "1_1") (pintype "passive"))
    )
    (net (code "59") (name "Net-(D10-A)") (class "Default")
      (node (ref "D10") (pin "2") (pinfunction "A_2") (pintype "passive"))
      (node (ref "R2") (pin "1") (pinfunction "1_1") (pintype "passive"))
    )
    (net (code "60") (name "Net-(IC1A-PB2)") (class "Default")
      (node (ref "IC1") (pin "20") (pinfunction "PB2_20") (pintype "passive"))
      (node (ref "R26") (pin "1") (pinfunction "1_1") (pintype "passive"))
    )
    (net (code "61") (name "Net-(IC1A-PB3)") (class "Default")
      (node (ref "IC1") (pin "39") (pinfunction "PB3_39") (pintype "passive"))
      (node (ref "R62") (pin "1") (pinfunction "1_1") (pintype "passive"))
    )
    (net (code "62") (name "Net-(IC1A-PB4)") (class "Default")
      (node (ref "IC1") (pin "40") (pinfunction "PB4_40") (pintype "passive"))
      (node (ref "R68") (pin "1") (pinfunction "1_1") (pintype "passive"))
    )
    (net (code "63") (name "Net-(IC1A-PB14)") (class "Default")
      (node (ref "IC1") (pin "27") (pinfunction "PB14_27") (pintype "passive"))
      (node (ref "R61") (pin "1") (pinfunction "1_1") (pintype "passive"))
    )
    (net (code "64") (name "Net-(IC1A-PB15)") (class "Default")
      (node (ref "IC1") (pin "28") (pinfunction "PB15_28") (pintype "passive"))
      (node (ref "R82") (pin "1") (pinfunction "1_1") (pintype "passive"))
    )
    (net (code "65") (name "Net-(IC1A-PD0-OSC_IN)") (class "Default")
      (node (ref "C6") (pin "1") (pinfunction "1_1") (pintype "passive"))
      (node (ref "IC1") (pin "5") (pinfunction "PD0-OSC_IN_5") (pintype "passive"))
      (node (ref "Y1") (pin "1") (pinfunction "OSC1_1") (pintype "passive"))
    )
    (net (code "66") (name "Net-(IC1A-PD1)") (class "Default")
      (node (ref "C10") (pin "1") (pinfunction "1_1") (pintype "passive"))
      (node (ref "IC1") (pin "6") (pinfunction "PD1_6") (pintype "passive"))
      (node (ref "Y1") (pin "2") (pinfunction "OSC2_2") (pintype "passive"))
    )
    (net (code "67") (name "Net-(IC2-OutA)") (class "Default")
      (node (ref "IC2") (pin "15") (pinfunction "OutA_15") (pintype "passive"))
      (node (ref "R11") (pin "2") (pinfunction "2_2") (pintype "passive"))
    )
    (net (code "68") (name "Net-(IC2-OutB)") (class "Default")
      (node (ref "IC2") (pin "1") (pinfunction "OutB_1") (pintype "passive"))
      (node (ref "R15") (pin "2") (pinfunction "2_2") (pintype "passive"))
    )
    (net (code "69") (name "Net-(IC2-OutC)") (class "Default")
      (node (ref "IC2") (pin "2") (pinfunction "OutC_2") (pintype "passive"))
      (node (ref "R18") (pin "2") (pinfunction "2_2") (pintype "passive"))
    )
    (net (code "70") (name "Net-(IC2-OutD)") (class "Default")
      (node (ref "IC2") (pin "3") (pinfunction "OutD_3") (pintype "passive"))
      (node (ref "R19") (pin "2") (pinfunction "2_2") (pintype "passive"))
    )
    (net (code "71") (name "Net-(IC2-OutE)") (class "Default")
      (node (ref "IC2") (pin "4") (pinfunction "OutE_4") (pintype "passive"))
      (node (ref "R20") (pin "2") (pinfunction "2_2") (pintype "passive"))
    )
    (net (code "72") (name "Net-(IC2-OutF)") (class "Default")
      (node (ref "IC2") (pin "5") (pinfunction "OutF_5") (pintype "passive"))
      (node (ref "R9") (pin "1") (pinfunction "1_1") (pintype "passive"))
    )
    (net (code "73") (name "Net-(IC2-OutG)") (class "Default")
      (node (ref "IC2") (pin "6") (pinfunction "OutG_6") (pintype "passive"))
      (node (ref "R14") (pin "1") (pinfunction "1_1") (pintype "passive"))
    )
    (net (code "74") (name "Net-(IC2-OutH)") (class "Default")
      (node (ref "IC2") (pin "7") (pinfunction "OutH_7") (pintype "passive"))
      (node (ref "R17") (pin "1") (pinfunction "1_1") (pintype "passive"))
    )
    (net (code "75") (name "Net-(IC3-OutA)") (class "Default")
      (node (ref "IC3") (pin "15") (pinfunction "OutA_15") (pintype "passive"))
      (node (ref "R22") (pin "2") (pinfunction "2_2") (pintype "passive"))
    )
    (net (code "76") (name "Net-(IC3-OutB)") (class "Default")
      (node (ref "IC3") (pin "1") (pinfunction "OutB_1") (pintype "passive"))
      (node (ref "R27") (pin "2") (pinfunction "2_2") (pintype "passive"))
    )
    (net (code "77") (name "Net-(IC3-OutC)") (class "Default")
      (node (ref "IC3") (pin "2") (pinfunction "OutC_2") (pintype "passive"))
      (node (ref "R29") (pin "2") (pinfunction "2_2") (pintype "passive"))
    )
    (net (code "78") (name "Net-(IC3-OutD)") (class "Default")
      (node (ref "IC3") (pin "3") (pinfunction "OutD_3") (pintype "passive"))
      (node (ref "R30") (pin "2") (pinfunction "2_2") (pintype "passive"))
    )
    (net (code "79") (name "Net-(IC3-OutE)") (class "Default")
      (node (ref "IC3") (pin "4") (pinfunction "OutE_4") (pintype "passive"))
      (node (ref "R31") (pin "2") (pinfunction "2_2") (pintype "passive"))
    )
    (net (code "80") (name "Net-(IC3-OutF)") (class "Default")
      (node (ref "IC3") (pin "5") (pinfunction "OutF_5") (pintype "passive"))
      (node (ref "R21") (pin "1") (pinfunction "1_1") (pintype "passive"))
    )
    (net (code "81") (name "Net-(IC3-OutG)") (class "Default")
      (node (ref "IC3") (pin "6") (pinfunction "OutG_6") (pintype "passive"))
      (node (ref "R25") (pin "1") (pinfunction "1_1") (pintype "passive"))
    )
    (net (code "82") (name "Net-(IC3-OutH)") (class "Default")
      (node (ref "IC3") (pin "7") (pinfunction "OutH_7") (pintype "passive"))
      (node (ref "R28") (pin "1") (pinfunction "1_1") (pintype "passive"))
    )
    (net (code "83") (name "Net-(IC4-OutA)") (class "Default")
      (node (ref "IC4") (pin "15") (pinfunction "OutA_15") (pintype "passive"))
      (node (ref "R33") (pin "2") (pinfunction "2_2") (pintype "passive"))
    )
    (net (code "84") (name "Net-(IC4-OutB)") (class "Default")
      (node (ref "IC4") (pin "1") (pinfunction "OutB_1") (pintype "passive"))
      (node (ref "R35") (pin "2") (pinfunction "2_2") (pintype "passive"))
    )
    (net (code "85") (name "Net-(IC4-OutC)") (class "Default")
      (node (ref "IC4") (pin "2") (pinfunction "OutC_2") (pintype "passive"))
      (node (ref "R37") (pin "2") (pinfunction "2_2") (pintype "passive"))
    )
    (net (code "86") (name "Net-(IC4-OutD)") (class "Default")
      (node (ref "IC4") (pin "3") (pinfunction "OutD_3") (pintype "passive"))
      (node (ref "R38") (pin "2") (pinfunction "2_2") (pintype "passive"))
    )
    (net (code "87") (name "Net-(IC4-OutE)") (class "Default")
      (node (ref "IC4") (pin "4") (pinfunction "OutE_4") (pintype "passive"))
      (node (ref "R39") (pin "2") (pinfunction "2_2") (pintype "passive"))
    )
    (net (code "88") (name "Net-(IC4-OutF)") (class "Default")
      (node (ref "IC4") (pin "5") (pinfunction "OutF_5") (pintype "passive"))
      (node (ref "R32") (pin "1") (pinfunction "1_1") (pintype "passive"))
    )
    (net (code "89") (name "Net-(IC4-OutG)") (class "Default")
      (node (ref "IC4") (pin "6") (pinfunction "OutG_6") (pintype "passive"))
      (node (ref "R34") (pin "1") (pinfunction "1_1") (pintype "passive"))
    )
    (net (code "90") (name "Net-(IC4-OutH)") (class "Default")
      (node (ref "IC4") (pin "7") (pinfunction "OutH_7") (pintype "passive"))
      (node (ref "R36") (pin "1") (pinfunction "1_1") (pintype "passive"))
    )
    (net (code "91") (name "unconnected-(IC1A-PA0-WKUP-Pad10)") (class "Default")
      (node (ref "IC1") (pin "10") (pinfunction "PA0-WKUP_10") (pintype "passive+no_connect"))
    )
    (net (code "92") (name "unconnected-(IC1A-PA1-Pad11)") (class "Default")
      (node (ref "IC1") (pin "11") (pinfunction "PA1_11") (pintype "passive+no_connect"))
    )
    (net (code "93") (name "unconnected-(IC1A-PA8-Pad29)") (class "Default")
      (node (ref "IC1") (pin "29") (pinfunction "PA8_29") (pintype "passive+no_connect"))
    )
    (net (code "94") (name "unconnected-(IC1A-PA11-Pad32)") (class "Default")
      (node (ref "IC1") (pin "32") (pinfunction "PA11_32") (pintype "passive+no_connect"))
    )
    (net (code "95") (name "unconnected-(IC1A-PA12-Pad33)") (class "Default")
      (node (ref "IC1") (pin "33") (pinfunction "PA12_33") (pintype "passive+no_connect"))
    )
    (net (code "96") (name "unconnected-(IC1A-PA15-Pad38)") (class "Default")
      (node (ref "IC1") (pin "38") (pinfunction "PA15_38") (pintype "passive"))
    )
    (net (code "97") (name "unconnected-(IC1A-PB0-Pad18)") (class "Default")
      (node (ref "IC1") (pin "18") (pinfunction "PB0_18") (pintype "passive+no_connect"))
    )
    (net (code "98") (name "unconnected-(IC1A-PB1-Pad19)") (class "Default")
      (node (ref "IC1") (pin "19") (pinfunction "PB1_19") (pintype "passive+no_connect"))
    )
    (net (code "99") (name "unconnected-(IC1A-PC13-TAMPER-RTC-Pad2)") (class "Default")
      (node (ref "IC1") (pin "2") (pinfunction "PC13-TAMPER-RTC_2") (pintype "passive+no_connect"))
    )
    (net (code "100") (name "unconnected-(IC1A-PC14-OSC32_IN-Pad3)") (class "Default")
      (node (ref "IC1") (pin "3") (pinfunction "PC14-OSC32_IN_3") (pintype "passive+no_connect"))
    )
    (net (code "101") (name "unconnected-(IC1A-PC15-OSC32_OUT-Pad4)") (class "Default")
      (node (ref "IC1") (pin "4") (pinfunction "PC15-OSC32_OUT_4") (pintype "passive+no_connect"))
    )
    (net (code "102") (name "unconnected-(R26-Pad2)") (class "Default")
      (node (ref "R26") (pin "2") (pinfunction "2_2") (pintype "passive+no_connect"))
    )
  )
)
